# Justin_Ngo_u0453732_MotorPCB_Rev3.net
KiCad netlist of a schematic drawn in EAGLE
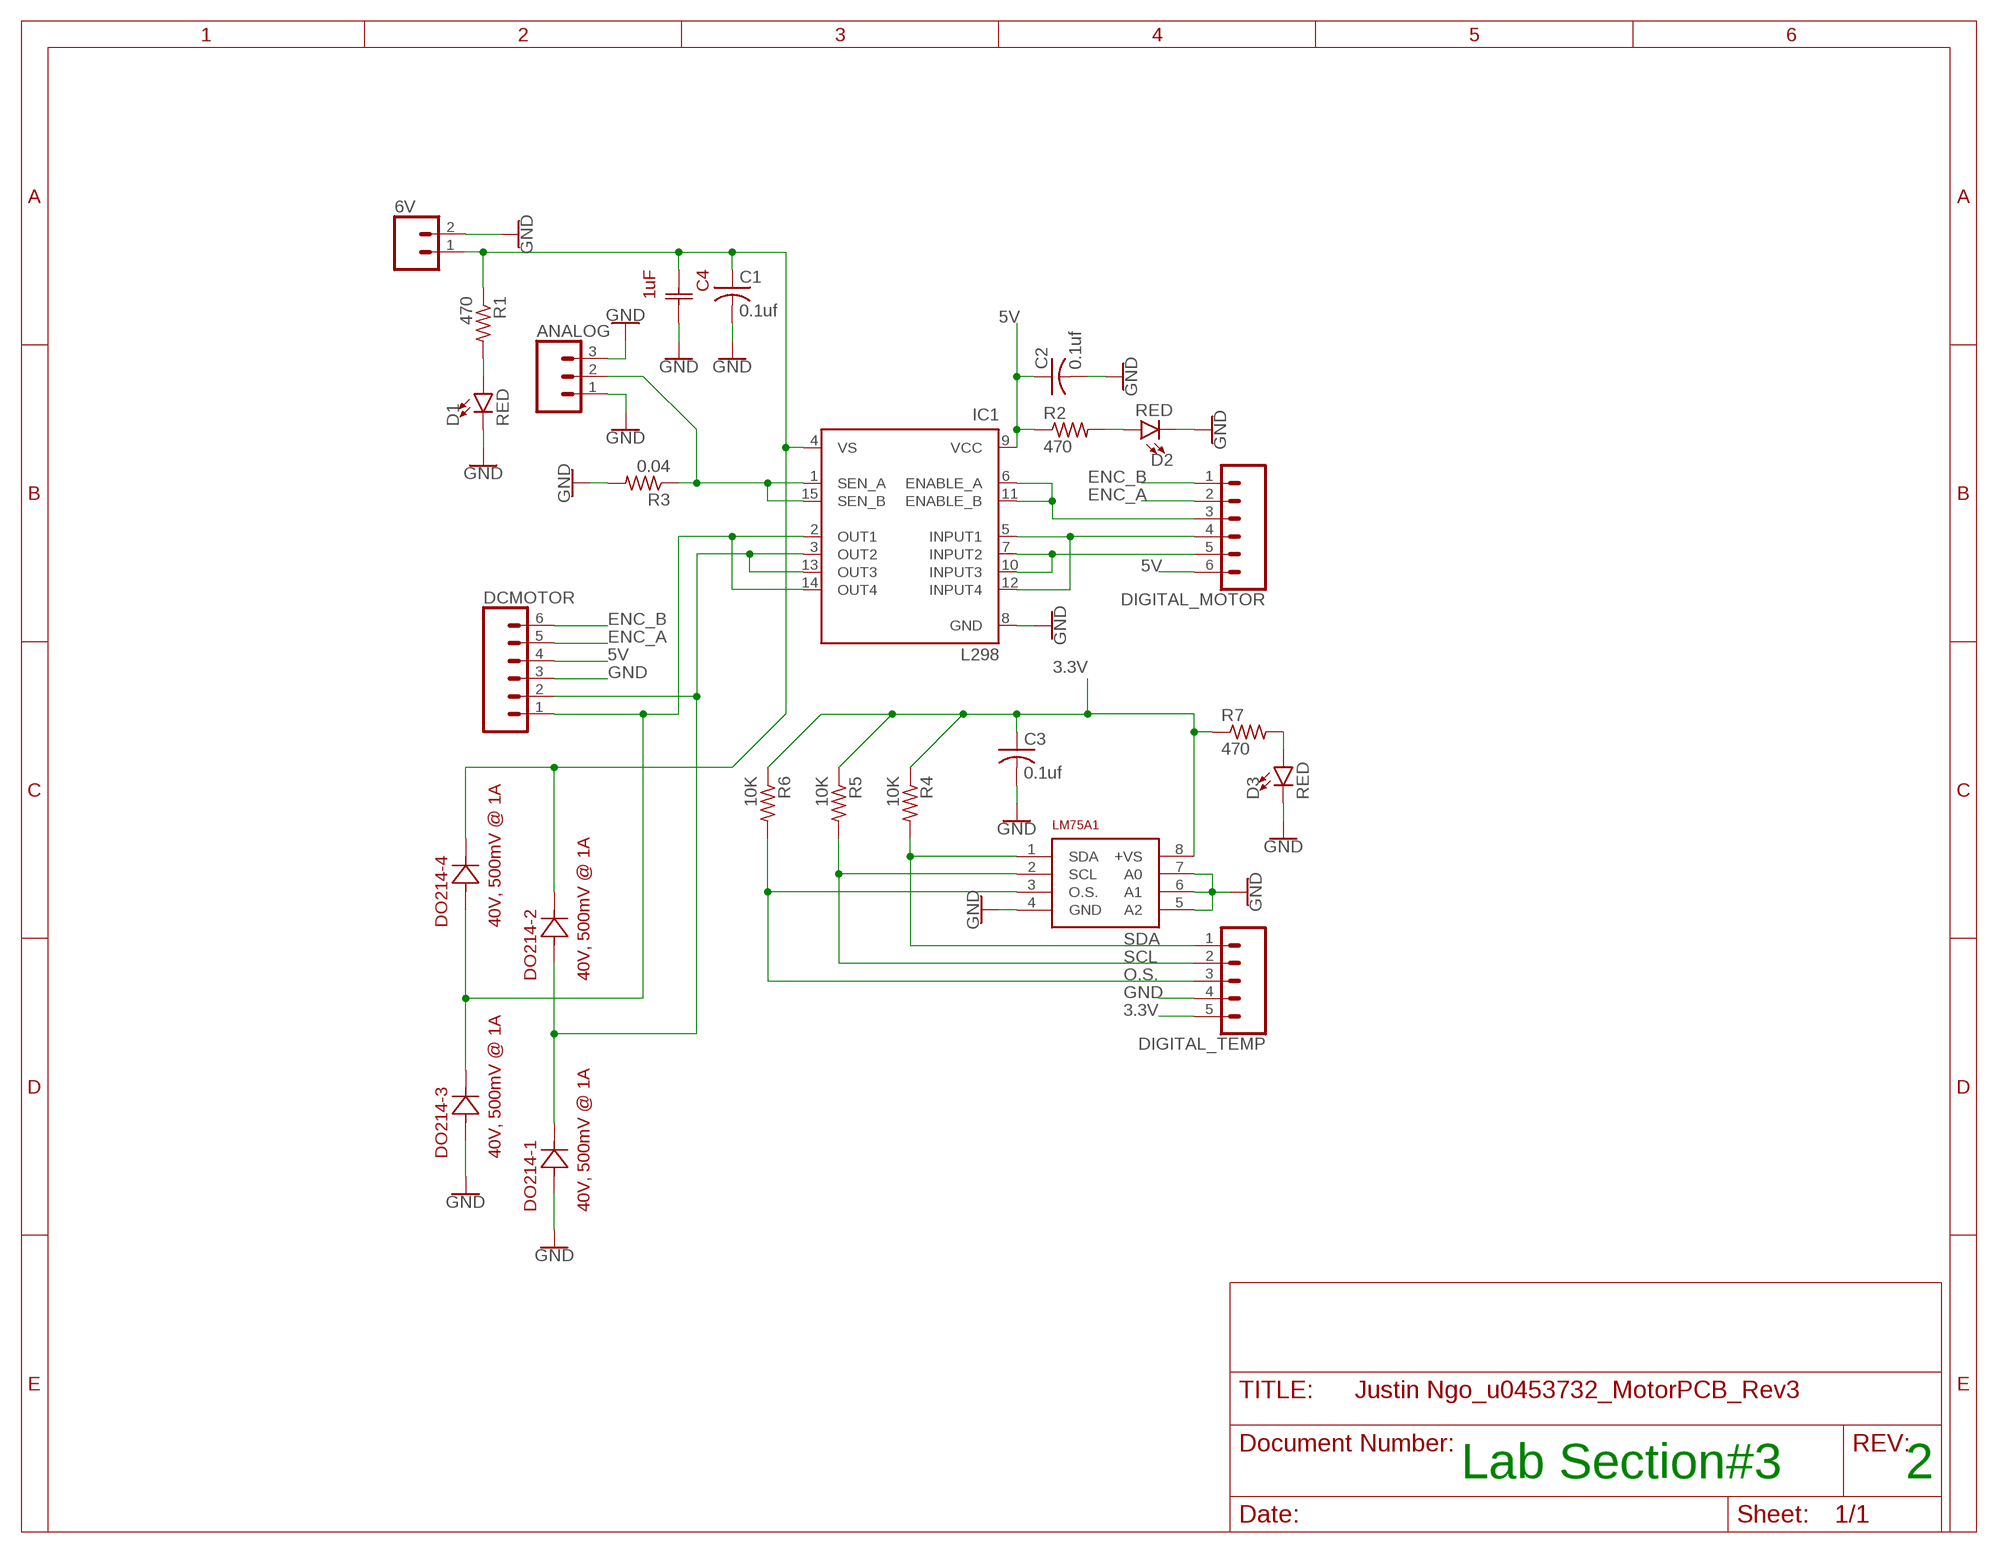
[diagram p0: schematic, sheet 1]

(export (version "E")
  (design (tool "Eeschema 10.0.6"))
  (components
    (comp (ref "6V")
      (value "CONN_025MM")
      (footprint "eagle-import:SCREWTERMINAL-5MM-2")
      (libsource (lib "eagle-import") (part "CONN_025MM"))
    )
    (comp (ref "ANALOG")
      (value "CONN_03")
      (footprint "eagle-import:1X03")
      (libsource (lib "eagle-import") (part "CONN_03"))
    )
    (comp (ref "C1")
      (value "0.1uf")
      (footprint "eagle-import:C1206")
      (libsource (lib "eagle-import") (part "C-USC1206"))
    )
    (comp (ref "C2")
      (value "0.1uf")
      (footprint "eagle-import:C1206")
      (libsource (lib "eagle-import") (part "C-USC1206"))
    )
    (comp (ref "C3")
      (value "0.1uf")
      (footprint "eagle-import:C1206")
      (libsource (lib "eagle-import") (part "C-USC1206"))
    )
    (comp (ref "C4")
      (value "1uF")
      (footprint "eagle-import:U1-E")
      (fields
        (field (name "MANUFACTURER_PART_NUMBER") "UVK1H010MDD1TD")
        (field (name "COPYRIGHT") "Copyright C 2015 Accelerated Designs. All rights reserved")
      )
      (libsource (lib "eagle-import") (part "UVK1H010MDD1TD"))
    )
    (comp (ref "D1")
      (value "RED")
      (footprint "eagle-import:LED-1206")
      (libsource (lib "eagle-import") (part "LED-RED1206"))
    )
    (comp (ref "D2")
      (value "RED")
      (footprint "eagle-import:LED-1206")
      (libsource (lib "eagle-import") (part "LED-RED1206"))
    )
    (comp (ref "D3")
      (value "RED")
      (footprint "eagle-import:LED-1206")
      (libsource (lib "eagle-import") (part "LED-RED1206"))
    )
    (comp (ref "DCMOTOR")
      (value "CONN_06LOCK_LONGPADS")
      (footprint "eagle-import:1X06_LOCK_LONGPADS")
      (libsource (lib "eagle-import") (part "CONN_06LOCK_LONGPADS"))
    )
    (comp (ref "DIGITAL_MOTOR")
      (value "CONN_06LOCK_LONGPADS")
      (footprint "eagle-import:1X06_LOCK_LONGPADS")
      (libsource (lib "eagle-import") (part "CONN_06LOCK_LONGPADS"))
    )
    (comp (ref "DIGITAL_TEMP")
      (value "CONN_05LOCK_LONGPADS")
      (footprint "eagle-import:1X05_LOCK_LONGPADS")
      (libsource (lib "eagle-import") (part "CONN_05LOCK_LONGPADS"))
    )
    (comp (ref "DO214-1")
      (value "40V, 500mV @ 1A")
      (footprint "eagle-import:DIODE_DO214AC")
      (fields
        (field (name "MANUFACTURER_PART_NUMBER") "SS14")
        (field (name "RSPARTNUMBER") "4470352")
        (field (name "COPYRIGHT") "Copyright C 2015 Accelerated Designs. All rights reserved")
      )
      (libsource (lib "eagle-import") (part "SS14"))
    )
    (comp (ref "DO214-2")
      (value "40V, 500mV @ 1A")
      (footprint "eagle-import:DIODE_DO214AC")
      (fields
        (field (name "MANUFACTURER_PART_NUMBER") "SS14")
        (field (name "RSPARTNUMBER") "4470352")
        (field (name "COPYRIGHT") "Copyright C 2015 Accelerated Designs. All rights reserved")
      )
      (libsource (lib "eagle-import") (part "SS14"))
    )
    (comp (ref "DO214-3")
      (value "40V, 500mV @ 1A")
      (footprint "eagle-import:DIODE_DO214AC")
      (fields
        (field (name "MANUFACTURER_PART_NUMBER") "SS14")
        (field (name "RSPARTNUMBER") "4470352")
        (field (name "COPYRIGHT") "Copyright C 2015 Accelerated Designs. All rights reserved")
      )
      (libsource (lib "eagle-import") (part "SS14"))
    )
    (comp (ref "DO214-4")
      (value "40V, 500mV @ 1A")
      (footprint "eagle-import:DIODE_DO214AC")
      (fields
        (field (name "MANUFACTURER_PART_NUMBER") "SS14")
        (field (name "RSPARTNUMBER") "4470352")
        (field (name "COPYRIGHT") "Copyright C 2015 Accelerated Designs. All rights reserved")
      )
      (libsource (lib "eagle-import") (part "SS14"))
    )
    (comp (ref "IC1")
      (value "L298")
      (footprint "eagle-import:MULTIWATT-15")
      (fields (field (name "MPN") "L298N"))
      (libsource (lib "eagle-import") (part "L298"))
    )
    (comp (ref "LM75A1")
      (value "TI-LM75A")
      (footprint "eagle-import:TI-LM75A")
      (libsource (lib "eagle-import") (part "TI-LM75A"))
    )
    (comp (ref "R1")
      (value "470")
      (footprint "eagle-import:R1206")
      (libsource (lib "eagle-import") (part "R-US_R1206"))
    )
    (comp (ref "R2")
      (value "470")
      (footprint "eagle-import:R1206")
      (libsource (lib "eagle-import") (part "R-US_R1206"))
    )
    (comp (ref "R3")
      (value "0.04")
      (footprint "eagle-import:R1206")
      (libsource (lib "eagle-import") (part "R-US_R1206"))
    )
    (comp (ref "R4")
      (value "10K")
      (footprint "eagle-import:R1206")
      (libsource (lib "eagle-import") (part "R-US_R1206"))
    )
    (comp (ref "R5")
      (value "10K")
      (footprint "eagle-import:R1206")
      (libsource (lib "eagle-import") (part "R-US_R1206"))
    )
    (comp (ref "R6")
      (value "10K")
      (footprint "eagle-import:R1206")
      (libsource (lib "eagle-import") (part "R-US_R1206"))
    )
    (comp (ref "R7")
      (value "470")
      (footprint "eagle-import:R1206")
      (libsource (lib "eagle-import") (part "R-US_R1206"))
    )
  )
  (nets
    (net (code "1") (name "/3.3V") (class "Default")
      (node (ref "C3") (pin "1") (pinfunction "1_1") (pintype "passive"))
      (node (ref "DIGITAL_TEMP") (pin "5") (pinfunction "5_5") (pintype "passive"))
      (node (ref "LM75A1") (pin "8") (pinfunction "+VS_8") (pintype "bidirectional"))
      (node (ref "R4") (pin "1") (pinfunction "1_1") (pintype "passive"))
      (node (ref "R5") (pin "1") (pinfunction "1_1") (pintype "passive"))
      (node (ref "R6") (pin "1") (pinfunction "1_1") (pintype "passive"))
      (node (ref "R7") (pin "1") (pinfunction "1_1") (pintype "passive"))
    )
    (net (code "2") (name "/5V") (class "Default")
      (node (ref "C2") (pin "1") (pinfunction "1_1") (pintype "passive"))
      (node (ref "DCMOTOR") (pin "4") (pinfunction "4_4") (pintype "passive"))
      (node (ref "DIGITAL_MOTOR") (pin "6") (pinfunction "6_6") (pintype "passive"))
      (node (ref "IC1") (pin "9") (pinfunction "VCC_9") (pintype "power_in"))
      (node (ref "R2") (pin "1") (pinfunction "1_1") (pintype "passive"))
    )
    (net (code "3") (name "/ENC_A") (class "Default")
      (node (ref "DCMOTOR") (pin "5") (pinfunction "5_5") (pintype "passive"))
      (node (ref "DIGITAL_MOTOR") (pin "2") (pinfunction "2_2") (pintype "passive"))
    )
    (net (code "4") (name "/ENC_B") (class "Default")
      (node (ref "DCMOTOR") (pin "6") (pinfunction "6_6") (pintype "passive"))
      (node (ref "DIGITAL_MOTOR") (pin "1") (pinfunction "1_1") (pintype "passive"))
    )
    (net (code "5") (name "/O.S.") (class "Default")
      (node (ref "DIGITAL_TEMP") (pin "3") (pinfunction "3_3") (pintype "passive"))
      (node (ref "LM75A1") (pin "3") (pinfunction "O.S._3") (pintype "bidirectional"))
      (node (ref "R6") (pin "2") (pinfunction "2_2") (pintype "passive"))
    )
    (net (code "6") (name "/SCL") (class "Default")
      (node (ref "DIGITAL_TEMP") (pin "2") (pinfunction "2_2") (pintype "passive"))
      (node (ref "LM75A1") (pin "2") (pinfunction "SCL_2") (pintype "bidirectional"))
      (node (ref "R5") (pin "2") (pinfunction "2_2") (pintype "passive"))
    )
    (net (code "7") (name "/SDA") (class "Default")
      (node (ref "DIGITAL_TEMP") (pin "1") (pinfunction "1_1") (pintype "passive"))
      (node (ref "LM75A1") (pin "1") (pinfunction "SDA_1") (pintype "bidirectional"))
      (node (ref "R4") (pin "2") (pinfunction "2_2") (pintype "passive"))
    )
    (net (code "8") (name "GND") (class "Default")
      (node (ref "6V") (pin "2") (pinfunction "2_2") (pintype "passive"))
      (node (ref "ANALOG") (pin "1") (pinfunction "1_1") (pintype "passive"))
      (node (ref "ANALOG") (pin "3") (pinfunction "3_3") (pintype "passive"))
      (node (ref "C1") (pin "2") (pinfunction "2_2") (pintype "passive"))
      (node (ref "C2") (pin "2") (pinfunction "2_2") (pintype "passive"))
      (node (ref "C3") (pin "2") (pinfunction "2_2") (pintype "passive"))
      (node (ref "C4") (pin "2") (pinfunction "22_2") (pintype "passive"))
      (node (ref "D1") (pin "C") (pinfunction "C_C") (pintype "passive"))
      (node (ref "D2") (pin "C") (pinfunction "C_C") (pintype "passive"))
      (node (ref "D3") (pin "C") (pinfunction "C_C") (pintype "passive"))
      (node (ref "DCMOTOR") (pin "3") (pinfunction "3_3") (pintype "passive"))
      (node (ref "DIGITAL_TEMP") (pin "4") (pinfunction "4_4") (pintype "passive"))
      (node (ref "DO214-1") (pin "2") (pinfunction "21_2") (pintype "passive"))
      (node (ref "DO214-3") (pin "2") (pinfunction "21_2") (pintype "passive"))
      (node (ref "IC1") (pin "8") (pinfunction "GND_8") (pintype "power_in"))
      (node (ref "LM75A1") (pin "4") (pinfunction "GND_4") (pintype "bidirectional"))
      (node (ref "LM75A1") (pin "5") (pinfunction "A2_5") (pintype "bidirectional"))
      (node (ref "LM75A1") (pin "6") (pinfunction "A1_6") (pintype "bidirectional"))
      (node (ref "LM75A1") (pin "7") (pinfunction "A0_7") (pintype "bidirectional"))
      (node (ref "R3") (pin "2") (pinfunction "2_2") (pintype "passive"))
    )
    (net (code "9") (name "Net-(C4-11)") (class "Default")
      (node (ref "6V") (pin "1") (pinfunction "1_1") (pintype "passive"))
      (node (ref "C1") (pin "1") (pinfunction "1_1") (pintype "passive"))
      (node (ref "C4") (pin "1") (pinfunction "11_1") (pintype "passive"))
      (node (ref "DO214-2") (pin "1") (pinfunction "12_1") (pintype "passive"))
      (node (ref "DO214-4") (pin "1") (pinfunction "12_1") (pintype "passive"))
      (node (ref "IC1") (pin "4") (pinfunction "VS_4") (pintype "power_in"))
      (node (ref "R1") (pin "1") (pinfunction "1_1") (pintype "passive"))
    )
    (net (code "10") (name "Net-(D1-PadA)") (class "Default")
      (node (ref "D1") (pin "A") (pinfunction "A_A") (pintype "passive"))
      (node (ref "R1") (pin "2") (pinfunction "2_2") (pintype "passive"))
    )
    (net (code "11") (name "Net-(D2-PadA)") (class "Default")
      (node (ref "D2") (pin "A") (pinfunction "A_A") (pintype "passive"))
      (node (ref "R2") (pin "2") (pinfunction "2_2") (pintype "passive"))
    )
    (net (code "12") (name "Net-(D3-PadA)") (class "Default")
      (node (ref "D3") (pin "A") (pinfunction "A_A") (pintype "passive"))
      (node (ref "R7") (pin "2") (pinfunction "2_2") (pintype "passive"))
    )
    (net (code "13") (name "Net-(DO214-1-12)") (class "Default")
      (node (ref "DCMOTOR") (pin "2") (pinfunction "2_2") (pintype "passive"))
      (node (ref "DO214-1") (pin "1") (pinfunction "12_1") (pintype "passive"))
      (node (ref "DO214-2") (pin "2") (pinfunction "21_2") (pintype "passive"))
      (node (ref "IC1") (pin "13") (pinfunction "OUT3_13") (pintype "output"))
      (node (ref "IC1") (pin "3") (pinfunction "OUT2_3") (pintype "output"))
    )
    (net (code "14") (name "Net-(DO214-3-12)") (class "Default")
      (node (ref "DCMOTOR") (pin "1") (pinfunction "1_1") (pintype "passive"))
      (node (ref "DO214-3") (pin "1") (pinfunction "12_1") (pintype "passive"))
      (node (ref "DO214-4") (pin "2") (pinfunction "21_2") (pintype "passive"))
      (node (ref "IC1") (pin "14") (pinfunction "OUT4_14") (pintype "output"))
      (node (ref "IC1") (pin "2") (pinfunction "OUT1_2") (pintype "output"))
    )
    (net (code "15") (name "Net-(IC1-ENABLE_A)") (class "Default")
      (node (ref "DIGITAL_MOTOR") (pin "3") (pinfunction "3_3") (pintype "passive"))
      (node (ref "IC1") (pin "11") (pinfunction "ENABLE_B_11") (pintype "input"))
      (node (ref "IC1") (pin "6") (pinfunction "ENABLE_A_6") (pintype "input"))
    )
    (net (code "16") (name "Net-(IC1-INPUT1)") (class "Default")
      (node (ref "DIGITAL_MOTOR") (pin "4") (pinfunction "4_4") (pintype "passive"))
      (node (ref "IC1") (pin "12") (pinfunction "INPUT4_12") (pintype "input"))
      (node (ref "IC1") (pin "5") (pinfunction "INPUT1_5") (pintype "input"))
    )
    (net (code "17") (name "Net-(IC1-INPUT2)") (class "Default")
      (node (ref "DIGITAL_MOTOR") (pin "5") (pinfunction "5_5") (pintype "passive"))
      (node (ref "IC1") (pin "10") (pinfunction "INPUT3_10") (pintype "input"))
      (node (ref "IC1") (pin "7") (pinfunction "INPUT2_7") (pintype "input"))
    )
    (net (code "18") (name "Net-(IC1-SEN_A)") (class "Default")
      (node (ref "ANALOG") (pin "2") (pinfunction "2_2") (pintype "passive"))
      (node (ref "IC1") (pin "1") (pinfunction "SEN_A_1") (pintype "input"))
      (node (ref "IC1") (pin "15") (pinfunction "SEN_B_15") (pintype "input"))
      (node (ref "R3") (pin "1") (pinfunction "1_1") (pintype "passive"))
    )
  )
)
